# ProPrj_TTL2485_2025-05-29.net
KiCad netlist of a schematic drawn in EasyEDA Pro
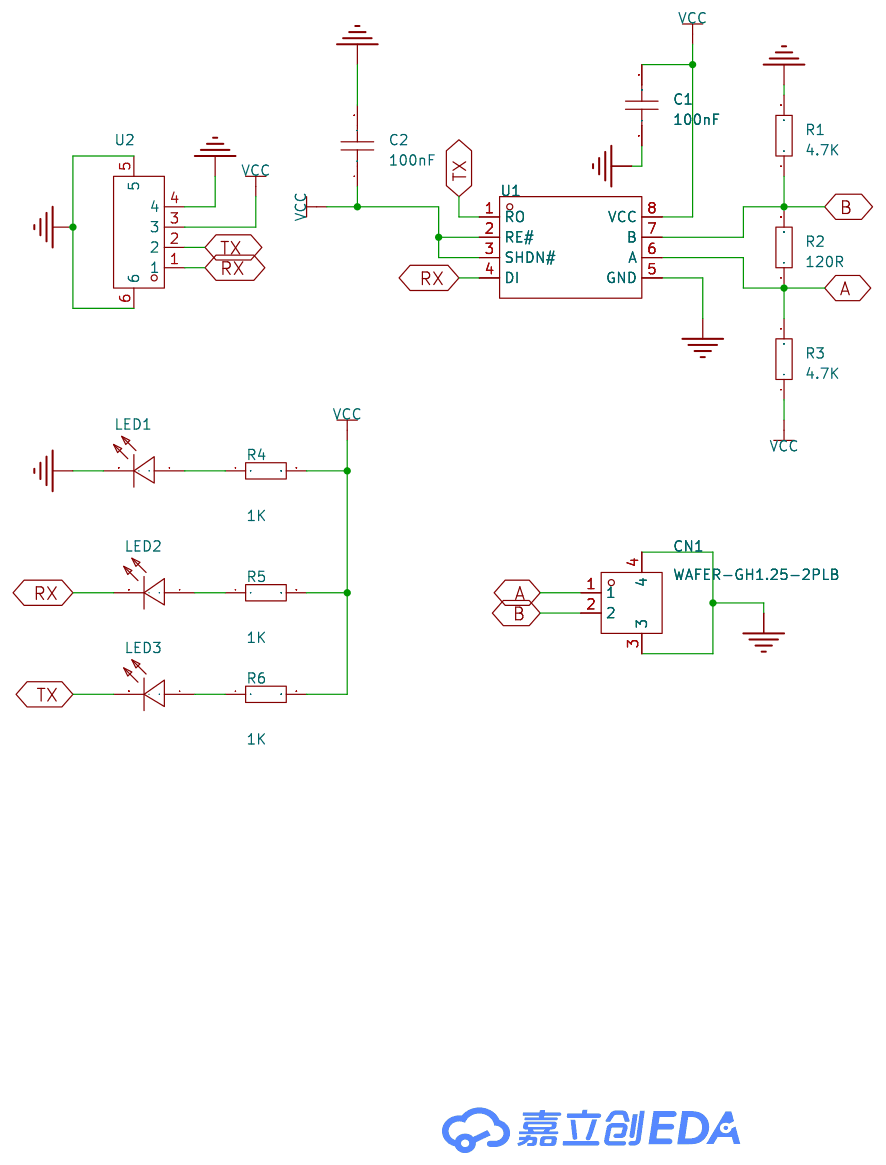
[diagram p0: schematic sheet]

(export (version "E")
  (design (tool "Eeschema 10.0.6"))
  (components
    (comp (ref "C1")
      (value "100nF")
      (footprint "easyedapro:C0402")
      (libsource (lib "easyedapro") (part "CapAcitance"))
    )
    (comp (ref "C2")
      (value "100nF")
      (footprint "easyedapro:C0402")
      (libsource (lib "easyedapro") (part "CapAcitance"))
    )
    (comp (ref "CN1")
      (value "WAFER-GH1.25-2PLB")
      (footprint "easyedapro:CONN-TH_2P-P1.25_XUNPU_WAFER-GH1.25-2PLB")
      (fields (field (name "Manufacturer") "XUNPU(讯普)"))
      (libsource (lib "easyedapro") (part "WAFER-GH1.25-2PLB"))
    )
    (comp (ref "LED1")
      (value "PWR")
      (footprint "easyedapro:LED0603-R-RD")
      (fields (field (name "Manufacturer Part") "SZYY0603R") (field (name "Manufacturer") "yongyu(永裕光电)"))
      (libsource (lib "easyedapro") (part "SZYY0603R"))
    )
    (comp (ref "LED2")
      (value "RX")
      (footprint "easyedapro:LED0603-R-RD")
      (fields (field (name "Manufacturer Part") "SZYY0603R") (field (name "Manufacturer") "yongyu(永裕光电)"))
      (libsource (lib "easyedapro") (part "SZYY0603R"))
    )
    (comp (ref "LED3")
      (value "TX")
      (footprint "easyedapro:LED0603-R-RD")
      (fields (field (name "Manufacturer Part") "SZYY0603R") (field (name "Manufacturer") "yongyu(永裕光电)"))
      (libsource (lib "easyedapro") (part "SZYY0603R"))
    )
    (comp (ref "R1") (value "4.7K") (footprint "easyedapro:R0402") (libsource (lib "easyedapro") (part "电阻")))
    (comp (ref "R2") (value "120R") (footprint "easyedapro:R0402") (libsource (lib "easyedapro") (part "电阻")))
    (comp (ref "R3") (value "4.7K") (footprint "easyedapro:R0402") (libsource (lib "easyedapro") (part "电阻")))
    (comp (ref "R4") (value "1K") (footprint "easyedapro:R0402") (libsource (lib "easyedapro") (part "电阻")))
    (comp (ref "R5") (value "1K") (footprint "easyedapro:R0402") (libsource (lib "easyedapro") (part "电阻")))
    (comp (ref "R6") (value "1K") (footprint "easyedapro:R0402") (libsource (lib "easyedapro") (part "电阻")))
    (comp (ref "U1")
      (value "COS13488EESA")
      (footprint "easyedapro:SOP-8_L4.9-W3.9-P1.27-LS6.0-BL")
      (description "具有自动方向控制,省去隔离控制通道，16Mbps，RS-485/RS-422 半双工收发器")
      (fields (field (name "Manufacturer") "COSINE(科山芯创)"))
      (libsource (lib "easyedapro") (part "COS13488EESA"))
    )
    (comp (ref "U2")
      (value "WAFER-GH1.25-4PLB")
      (footprint "easyedapro:CONN-SMD_4P-P1.25_XUNPU_WAFER-GH1.25-4PLB")
      (fields (field (name "Manufacturer") "XUNPU(讯普)"))
      (libsource (lib "easyedapro") (part "WAFER-GH1.25-4PLB"))
    )
  )
  (nets
    (net (code "1") (name "A") (class "Default")
      (node (ref "CN1") (pin "1") (pinfunction "1_1") (pintype "unspecified"))
      (node (ref "R2") (pin "1") (pinfunction "1_1") (pintype "input"))
      (node (ref "R3") (pin "2") (pinfunction "2_2") (pintype "input"))
      (node (ref "U1") (pin "6") (pinfunction "A_6") (pintype "unspecified"))
    )
    (net (code "2") (name "B") (class "Default")
      (node (ref "CN1") (pin "2") (pinfunction "2_2") (pintype "unspecified"))
      (node (ref "R1") (pin "1") (pinfunction "1_1") (pintype "input"))
      (node (ref "R2") (pin "2") (pinfunction "2_2") (pintype "input"))
      (node (ref "U1") (pin "7") (pinfunction "B_7") (pintype "unspecified"))
    )
    (net (code "3") (name "GND") (class "Default")
      (node (ref "C1") (pin "1") (pinfunction "1_1") (pintype "input"))
      (node (ref "C2") (pin "2") (pinfunction "2_2") (pintype "input"))
      (node (ref "CN1") (pin "3") (pinfunction "3_3") (pintype "unspecified"))
      (node (ref "CN1") (pin "4") (pinfunction "4_4") (pintype "unspecified"))
      (node (ref "LED1") (pin "2") (pinfunction "-_2") (pintype "unspecified"))
      (node (ref "R1") (pin "2") (pinfunction "2_2") (pintype "input"))
      (node (ref "U1") (pin "5") (pinfunction "GND_5") (pintype "unspecified"))
      (node (ref "U2") (pin "4") (pinfunction "4_4") (pintype "unspecified"))
      (node (ref "U2") (pin "5") (pinfunction "5_5") (pintype "unspecified"))
      (node (ref "U2") (pin "6") (pinfunction "6_6") (pintype "unspecified"))
    )
    (net (code "4") (name "Net-(LED1-+)") (class "Default")
      (node (ref "LED1") (pin "1") (pinfunction "+_1") (pintype "unspecified"))
      (node (ref "R4") (pin "1") (pinfunction "1_1") (pintype "input"))
    )
    (net (code "5") (name "Net-(LED2-+)") (class "Default")
      (node (ref "LED2") (pin "1") (pinfunction "+_1") (pintype "unspecified"))
      (node (ref "R5") (pin "1") (pinfunction "1_1") (pintype "input"))
    )
    (net (code "6") (name "Net-(LED3-+)") (class "Default")
      (node (ref "LED3") (pin "1") (pinfunction "+_1") (pintype "unspecified"))
      (node (ref "R6") (pin "1") (pinfunction "1_1") (pintype "input"))
    )
    (net (code "7") (name "RX") (class "Default")
      (node (ref "LED2") (pin "2") (pinfunction "-_2") (pintype "unspecified"))
      (node (ref "U1") (pin "4") (pinfunction "DI_4") (pintype "unspecified"))
      (node (ref "U2") (pin "1") (pinfunction "1_1") (pintype "unspecified"))
    )
    (net (code "8") (name "TX") (class "Default")
      (node (ref "LED3") (pin "2") (pinfunction "-_2") (pintype "unspecified"))
      (node (ref "U1") (pin "1") (pinfunction "RO_1") (pintype "unspecified"))
      (node (ref "U2") (pin "2") (pinfunction "2_2") (pintype "unspecified"))
    )
    (net (code "9") (name "VCC") (class "Default")
      (node (ref "C1") (pin "2") (pinfunction "2_2") (pintype "input"))
      (node (ref "C2") (pin "1") (pinfunction "1_1") (pintype "input"))
      (node (ref "R3") (pin "1") (pinfunction "1_1") (pintype "input"))
      (node (ref "R4") (pin "2") (pinfunction "2_2") (pintype "input"))
      (node (ref "R5") (pin "2") (pinfunction "2_2") (pintype "input"))
      (node (ref "R6") (pin "2") (pinfunction "2_2") (pintype "input"))
      (node (ref "U1") (pin "2") (pinfunction "RE#_2") (pintype "unspecified"))
      (node (ref "U1") (pin "3") (pinfunction "SHDN#_3") (pintype "unspecified"))
      (node (ref "U1") (pin "8") (pinfunction "VCC_8") (pintype "unspecified"))
      (node (ref "U2") (pin "3") (pinfunction "3_3") (pintype "unspecified"))
    )
  )
)
